# Brightside_Telemetry_power_rev2.net
KiCad netlist of a schematic drawn in Altium Designer
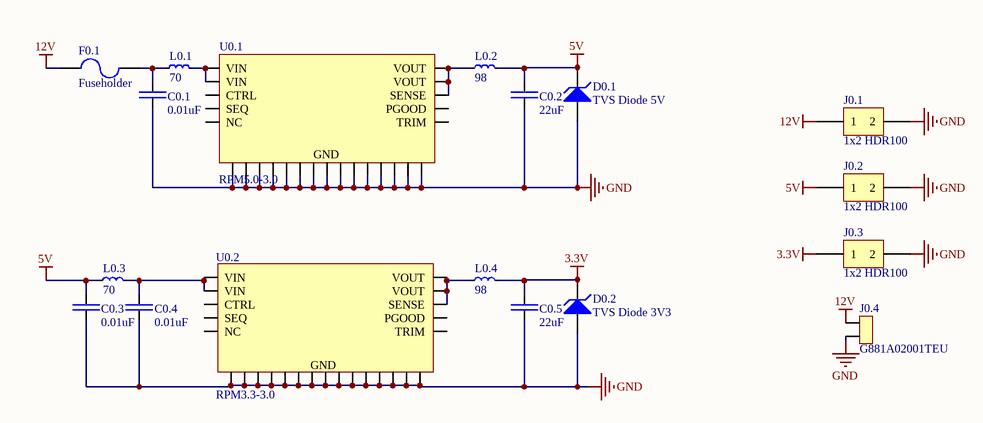
[diagram p0: Brightside_Telemetry_power_rev2.SchDoc]

(export (version "E")
  (design (tool "Eeschema 10.0.6"))
  (components
    (comp (ref "C0.1")
      (value "0.01uF")
      (footprint "0805")
      (description "Cap Ceramic 0.01uF 100V X7R 10% SMD 0805 125C T/R")
      (fields
        (field (name "MANUFACTURER") "KEMET")
        (field (name "MANUFACTURER PART NUMBER") "C0805C103K1RAC7210")
      )
      (libsource (lib "Capacitors") (part "C0805C103K1RAC7210"))
    )
    (comp (ref "C0.2")
      (value "22uF")
      (footprint "1206")
      (description "CAP CER 22UF 10V X7R 1206")
      (fields
        (field (name "MANUFACTURER") "Samsung")
        (field (name "MANUFACTURER PART NUMBER") "CL31B226KPHNNNE")
      )
      (libsource (lib "Capacitors") (part "CL31B226KPHNNNE"))
    )
    (comp (ref "C0.3")
      (value "0.01uF")
      (footprint "0805")
      (description "Cap Ceramic 0.01uF 100V X7R 10% SMD 0805 125C T/R")
      (fields
        (field (name "MANUFACTURER") "KEMET")
        (field (name "MANUFACTURER PART NUMBER") "C0805C103K1RAC7210")
      )
      (libsource (lib "Capacitors") (part "C0805C103K1RAC7210"))
    )
    (comp (ref "C0.4")
      (value "0.01uF")
      (footprint "0805")
      (description "Cap Ceramic 0.01uF 100V X7R 10% SMD 0805 125C T/R")
      (fields
        (field (name "MANUFACTURER") "KEMET")
        (field (name "MANUFACTURER PART NUMBER") "C0805C103K1RAC7210")
      )
      (libsource (lib "Capacitors") (part "C0805C103K1RAC7210"))
    )
    (comp (ref "C0.5")
      (value "22uF")
      (footprint "1206")
      (description "CAP CER 22UF 10V X7R 1206")
      (fields
        (field (name "MANUFACTURER") "Samsung")
        (field (name "MANUFACTURER PART NUMBER") "CL31B226KPHNNNE")
      )
      (libsource (lib "Capacitors") (part "CL31B226KPHNNNE"))
    )
    (comp (ref "D0.1")
      (value "TVS Diode 5V")
      (footprint "SOD-323")
      (description "TVS DIODE 5V 9.8V SOD323")
      (fields
        (field (name "MANUFACTURER") "ON Semiconductor")
        (field (name "MANUFACTURER PART NUMBER") "SD05T1G")
      )
      (libsource (lib "Diodes") (part "SD05T1G"))
    )
    (comp (ref "D0.2")
      (value "TVS Diode 3V3")
      (footprint "SOD-323")
      (description "ESD Suppressor TVS ±30kV 2-Pin SOD-323 T/R")
      (fields
        (field (name "MANUFACTURER") "Bourns")
        (field (name "MANUFACTURER PART NUMBER") "CDSOD323-T03S")
      )
      (libsource (lib "Diodes") (part "CDSOD323-T03S"))
    )
    (comp (ref "F0.1")
      (value "Fuseholder")
      (footprint "SCHURTER - 0031.7701.11 - FUSE HOLDER, PCB MOUNT")
      (description "SCHURTER - 0031.7701.11 - FUSE HOLDER, PCB MOUNT")
      (fields
        (field (name "MANUFACTURER") "Schurter")
        (field (name "MANUFACTURER PART NUMBER") "0031.7701.11")
      )
      (libsource (lib "Fuses & Holders") (part "0031.7701.11"))
    )
    (comp (ref "J0.1")
      (value "1x2 HDR100")
      (footprint "Molex 0901200762")
      (description "CONN HEADER VERT 2POS 2.54MM")
      (fields (field (name "MANUFACTURER") "Molex") (field (name "MANUFACTURER PART NUMBER") "0901200762"))
      (libsource (lib "Connectors") (part "0901200762"))
    )
    (comp (ref "J0.2")
      (value "1x2 HDR100")
      (footprint "Molex 0901200762")
      (description "CONN HEADER VERT 2POS 2.54MM")
      (fields (field (name "MANUFACTURER") "Molex") (field (name "MANUFACTURER PART NUMBER") "0901200762"))
      (libsource (lib "Connectors") (part "0901200762"))
    )
    (comp (ref "J0.3")
      (value "1x2 HDR100")
      (footprint "Molex 0901200762")
      (description "CONN HEADER VERT 2POS 2.54MM")
      (fields (field (name "MANUFACTURER") "Molex") (field (name "MANUFACTURER PART NUMBER") "0901200762"))
      (libsource (lib "Connectors") (part "0901200762"))
    )
    (comp (ref "J0.4")
      (value "G881A02001TEU")
      (footprint "Micro-Fit 3.0 2pos")
      (description "Micro-fit 3.0 2pos right-angle")
      (fields (field (name "MANUFACTURER") "Molex") (field (name "MANUFACTURER PART NUMBER") "0430450200"))
      (libsource (lib "Connectors") (part "G881A02001TEU"))
    )
    (comp (ref "L0.1")
      (value "70")
      (footprint "1812")
      (description "WURTH ELEKTRONIK - 742792510 - FERRITE BEAD, 70R, 6A, 1812")
      (fields
        (field (name "MANUFACTURER") "Wurth Electronics")
        (field (name "MANUFACTURER PART NUMBER") "742792510")
      )
      (libsource (lib "Inductors") (part "742792510"))
    )
    (comp (ref "L0.2")
      (value "98")
      (footprint "7427932")
      (description "Ferrite Bead 98 Ohm 2SMD 1LN")
      (fields
        (field (name "MANUFACTURER") "Wurth Electronics")
        (field (name "MANUFACTURER PART NUMBER") "7427932")
      )
      (libsource (lib "Inductors") (part "7427932"))
    )
    (comp (ref "L0.3")
      (value "70")
      (footprint "1812")
      (description "WURTH ELEKTRONIK - 742792510 - FERRITE BEAD, 70R, 6A, 1812")
      (fields
        (field (name "MANUFACTURER") "Wurth Electronics")
        (field (name "MANUFACTURER PART NUMBER") "742792510")
      )
      (libsource (lib "Inductors") (part "742792510"))
    )
    (comp (ref "L0.4")
      (value "98")
      (footprint "7427932")
      (description "Ferrite Bead 98 Ohm 2SMD 1LN")
      (fields
        (field (name "MANUFACTURER") "Wurth Electronics")
        (field (name "MANUFACTURER PART NUMBER") "7427932")
      )
      (libsource (lib "Inductors") (part "7427932"))
    )
    (comp (ref "U0.1")
      (value "RPM5.0-3.0")
      (footprint "25-BLGA")
      (description "DC-DC Converter; SMD; reg; Single Output; 3A; 5V Out; RPM-3.0 Series")
      (fields (field (name "MANUFACTURER") "Recom"))
      (libsource (lib "schem_lib") (part "RPM5.0-3.0"))
    )
    (comp (ref "U0.2")
      (value "RPM3.3-3.0")
      (footprint "25-BLGA")
      (description "RPM-3.0 Series 3 to 17 V Input 3.3 V Output 3 A Non Isolated DC/DC Converter")
      (fields (field (name "MANUFACTURER") "Recom"))
      (libsource (lib "schem_lib") (part "RPM3.3-3.0"))
    )
  )
  (nets
    (net (code "1") (name "3.3V") (class "Default")
      (node (ref "C0.5") (pin "2") (pinfunction "2_2") (pintype "passive"))
      (node (ref "D0.2") (pin "2") (pinfunction "K_2") (pintype "passive"))
      (node (ref "J0.3") (pin "1") (pinfunction "1_1") (pintype "passive"))
      (node (ref "L0.4") (pin "2") (pinfunction "2_2") (pintype "passive"))
    )
    (net (code "2") (name "5V") (class "Default")
      (node (ref "C0.2") (pin "2") (pinfunction "2_2") (pintype "passive"))
      (node (ref "C0.3") (pin "2") (pinfunction "2_2") (pintype "passive"))
      (node (ref "D0.1") (pin "2") (pinfunction "K_2") (pintype "passive"))
      (node (ref "J0.2") (pin "1") (pinfunction "1_1") (pintype "passive"))
      (node (ref "L0.2") (pin "2") (pinfunction "2_2") (pintype "passive"))
      (node (ref "L0.3") (pin "1") (pinfunction "1_1") (pintype "passive"))
    )
    (net (code "3") (name "12V") (class "Default")
      (node (ref "F0.1") (pin "1") (pinfunction "1_1") (pintype "passive"))
      (node (ref "J0.1") (pin "1") (pinfunction "1_1") (pintype "passive"))
      (node (ref "J0.4") (pin "1") (pinfunction "1_1") (pintype "passive"))
    )
    (net (code "4") (name "GND") (class "Default")
      (node (ref "C0.1") (pin "1") (pinfunction "1_1") (pintype "passive"))
      (node (ref "C0.2") (pin "1") (pinfunction "1_1") (pintype "passive"))
      (node (ref "C0.3") (pin "1") (pinfunction "1_1") (pintype "passive"))
      (node (ref "C0.4") (pin "1") (pinfunction "1_1") (pintype "passive"))
      (node (ref "C0.5") (pin "1") (pinfunction "1_1") (pintype "passive"))
      (node (ref "D0.1") (pin "1") (pinfunction "A_1") (pintype "passive"))
      (node (ref "D0.2") (pin "1") (pinfunction "A_1") (pintype "passive"))
      (node (ref "J0.1") (pin "2") (pinfunction "2_2") (pintype "passive"))
      (node (ref "J0.2") (pin "2") (pinfunction "2_2") (pintype "passive"))
      (node (ref "J0.3") (pin "2") (pinfunction "2_2") (pintype "passive"))
      (node (ref "J0.4") (pin "2") (pinfunction "2_2") (pintype "passive"))
      (node (ref "U0.1") (pin "A3") (pinfunction "GND_A3") (pintype "passive"))
      (node (ref "U0.1") (pin "A4") (pinfunction "GND_A4") (pintype "passive"))
      (node (ref "U0.1") (pin "B1") (pinfunction "GND_B1") (pintype "passive"))
      (node (ref "U0.1") (pin "B2") (pinfunction "GND_B2") (pintype "passive"))
      (node (ref "U0.1") (pin "B3") (pinfunction "GND_B3") (pintype "passive"))
      (node (ref "U0.1") (pin "B4") (pinfunction "GND_B4") (pintype "passive"))
      (node (ref "U0.1") (pin "C2") (pinfunction "GND_C2") (pintype "passive"))
      (node (ref "U0.1") (pin "C3") (pinfunction "GND_C3") (pintype "passive"))
      (node (ref "U0.1") (pin "C4") (pinfunction "GND_C4") (pintype "passive"))
      (node (ref "U0.1") (pin "D2") (pinfunction "GND_D2") (pintype "passive"))
      (node (ref "U0.1") (pin "D3") (pinfunction "GND_D3") (pintype "passive"))
      (node (ref "U0.1") (pin "D4") (pinfunction "GND_D4") (pintype "passive"))
      (node (ref "U0.1") (pin "D5") (pinfunction "GND_D5") (pintype "passive"))
      (node (ref "U0.1") (pin "E3") (pinfunction "GND_E3") (pintype "passive"))
      (node (ref "U0.1") (pin "E4") (pinfunction "GND_E4") (pintype "passive"))
      (node (ref "U0.2") (pin "A3") (pinfunction "GND_A3") (pintype "passive"))
      (node (ref "U0.2") (pin "A4") (pinfunction "GND_A4") (pintype "passive"))
      (node (ref "U0.2") (pin "B1") (pinfunction "GND_B1") (pintype "passive"))
      (node (ref "U0.2") (pin "B2") (pinfunction "GND_B2") (pintype "passive"))
      (node (ref "U0.2") (pin "B3") (pinfunction "GND_B3") (pintype "passive"))
      (node (ref "U0.2") (pin "B4") (pinfunction "GND_B4") (pintype "passive"))
      (node (ref "U0.2") (pin "C2") (pinfunction "GND_C2") (pintype "passive"))
      (node (ref "U0.2") (pin "C3") (pinfunction "GND_C3") (pintype "passive"))
      (node (ref "U0.2") (pin "C4") (pinfunction "GND_C4") (pintype "passive"))
      (node (ref "U0.2") (pin "D2") (pinfunction "GND_D2") (pintype "passive"))
      (node (ref "U0.2") (pin "D3") (pinfunction "GND_D3") (pintype "passive"))
      (node (ref "U0.2") (pin "D4") (pinfunction "GND_D4") (pintype "passive"))
      (node (ref "U0.2") (pin "D5") (pinfunction "GND_D5") (pintype "passive"))
      (node (ref "U0.2") (pin "E3") (pinfunction "GND_E3") (pintype "passive"))
      (node (ref "U0.2") (pin "E4") (pinfunction "GND_E4") (pintype "passive"))
    )
    (net (code "5") (name "Net-(C0.1-Pad2)") (class "Default")
      (node (ref "C0.1") (pin "2") (pinfunction "2_2") (pintype "passive"))
      (node (ref "F0.1") (pin "2") (pinfunction "2_2") (pintype "passive"))
      (node (ref "L0.1") (pin "1") (pinfunction "1_1") (pintype "passive"))
    )
    (net (code "6") (name "Net-(C0.4-Pad2)") (class "Default")
      (node (ref "C0.4") (pin "2") (pinfunction "2_2") (pintype "passive"))
      (node (ref "L0.3") (pin "2") (pinfunction "2_2") (pintype "passive"))
      (node (ref "U0.2") (pin "A1") (pinfunction "VIN_A1") (pintype "passive"))
      (node (ref "U0.2") (pin "A2") (pinfunction "VIN_A2") (pintype "passive"))
    )
    (net (code "7") (name "Net-(L0.1-Pad2)") (class "Default")
      (node (ref "L0.1") (pin "2") (pinfunction "2_2") (pintype "passive"))
      (node (ref "U0.1") (pin "A1") (pinfunction "VIN_A1") (pintype "passive"))
      (node (ref "U0.1") (pin "A2") (pinfunction "VIN_A2") (pintype "passive"))
    )
    (net (code "8") (name "Net-(U0.1-SENSE)") (class "Default")
      (node (ref "L0.2") (pin "1") (pinfunction "1_1") (pintype "passive"))
      (node (ref "U0.1") (pin "A5") (pinfunction "VOUT_A5") (pintype "passive"))
      (node (ref "U0.1") (pin "B5") (pinfunction "VOUT_B5") (pintype "passive"))
      (node (ref "U0.1") (pin "C5") (pinfunction "SENSE_C5") (pintype "passive"))
    )
    (net (code "9") (name "Net-(U0.2-SENSE)") (class "Default")
      (node (ref "L0.4") (pin "1") (pinfunction "1_1") (pintype "passive"))
      (node (ref "U0.2") (pin "A5") (pinfunction "VOUT_A5") (pintype "passive"))
      (node (ref "U0.2") (pin "B5") (pinfunction "VOUT_B5") (pintype "passive"))
      (node (ref "U0.2") (pin "C5") (pinfunction "SENSE_C5") (pintype "passive"))
    )
    (net (code "10") (name "unconnected-(U0.1-CTRL-PadC1)") (class "Default")
      (node (ref "U0.1") (pin "C1") (pinfunction "CTRL_C1") (pintype "passive"))
    )
    (net (code "11") (name "unconnected-(U0.1-NC-PadE2)") (class "Default")
      (node (ref "U0.1") (pin "E2") (pinfunction "NC_E2") (pintype "passive"))
    )
    (net (code "12") (name "unconnected-(U0.1-PGOOD-PadD1)") (class "Default")
      (node (ref "U0.1") (pin "D1") (pinfunction "PGOOD_D1") (pintype "passive"))
    )
    (net (code "13") (name "unconnected-(U0.1-SEQ-PadE1)") (class "Default")
      (node (ref "U0.1") (pin "E1") (pinfunction "SEQ_E1") (pintype "passive"))
    )
    (net (code "14") (name "unconnected-(U0.1-TRIM-PadE5)") (class "Default")
      (node (ref "U0.1") (pin "E5") (pinfunction "TRIM_E5") (pintype "passive"))
    )
    (net (code "15") (name "unconnected-(U0.2-CTRL-PadC1)") (class "Default")
      (node (ref "U0.2") (pin "C1") (pinfunction "CTRL_C1") (pintype "passive"))
    )
    (net (code "16") (name "unconnected-(U0.2-NC-PadE2)") (class "Default")
      (node (ref "U0.2") (pin "E2") (pinfunction "NC_E2") (pintype "passive"))
    )
    (net (code "17") (name "unconnected-(U0.2-PGOOD-PadD1)") (class "Default")
      (node (ref "U0.2") (pin "D1") (pinfunction "PGOOD_D1") (pintype "passive"))
    )
    (net (code "18") (name "unconnected-(U0.2-SEQ-PadE1)") (class "Default")
      (node (ref "U0.2") (pin "E1") (pinfunction "SEQ_E1") (pintype "passive"))
    )
    (net (code "19") (name "unconnected-(U0.2-TRIM-PadE5)") (class "Default")
      (node (ref "U0.2") (pin "E5") (pinfunction "TRIM_E5") (pintype "passive"))
    )
  )
)
